# ac_monitor.net
KiCad netlist of a schematic drawn in EAGLE
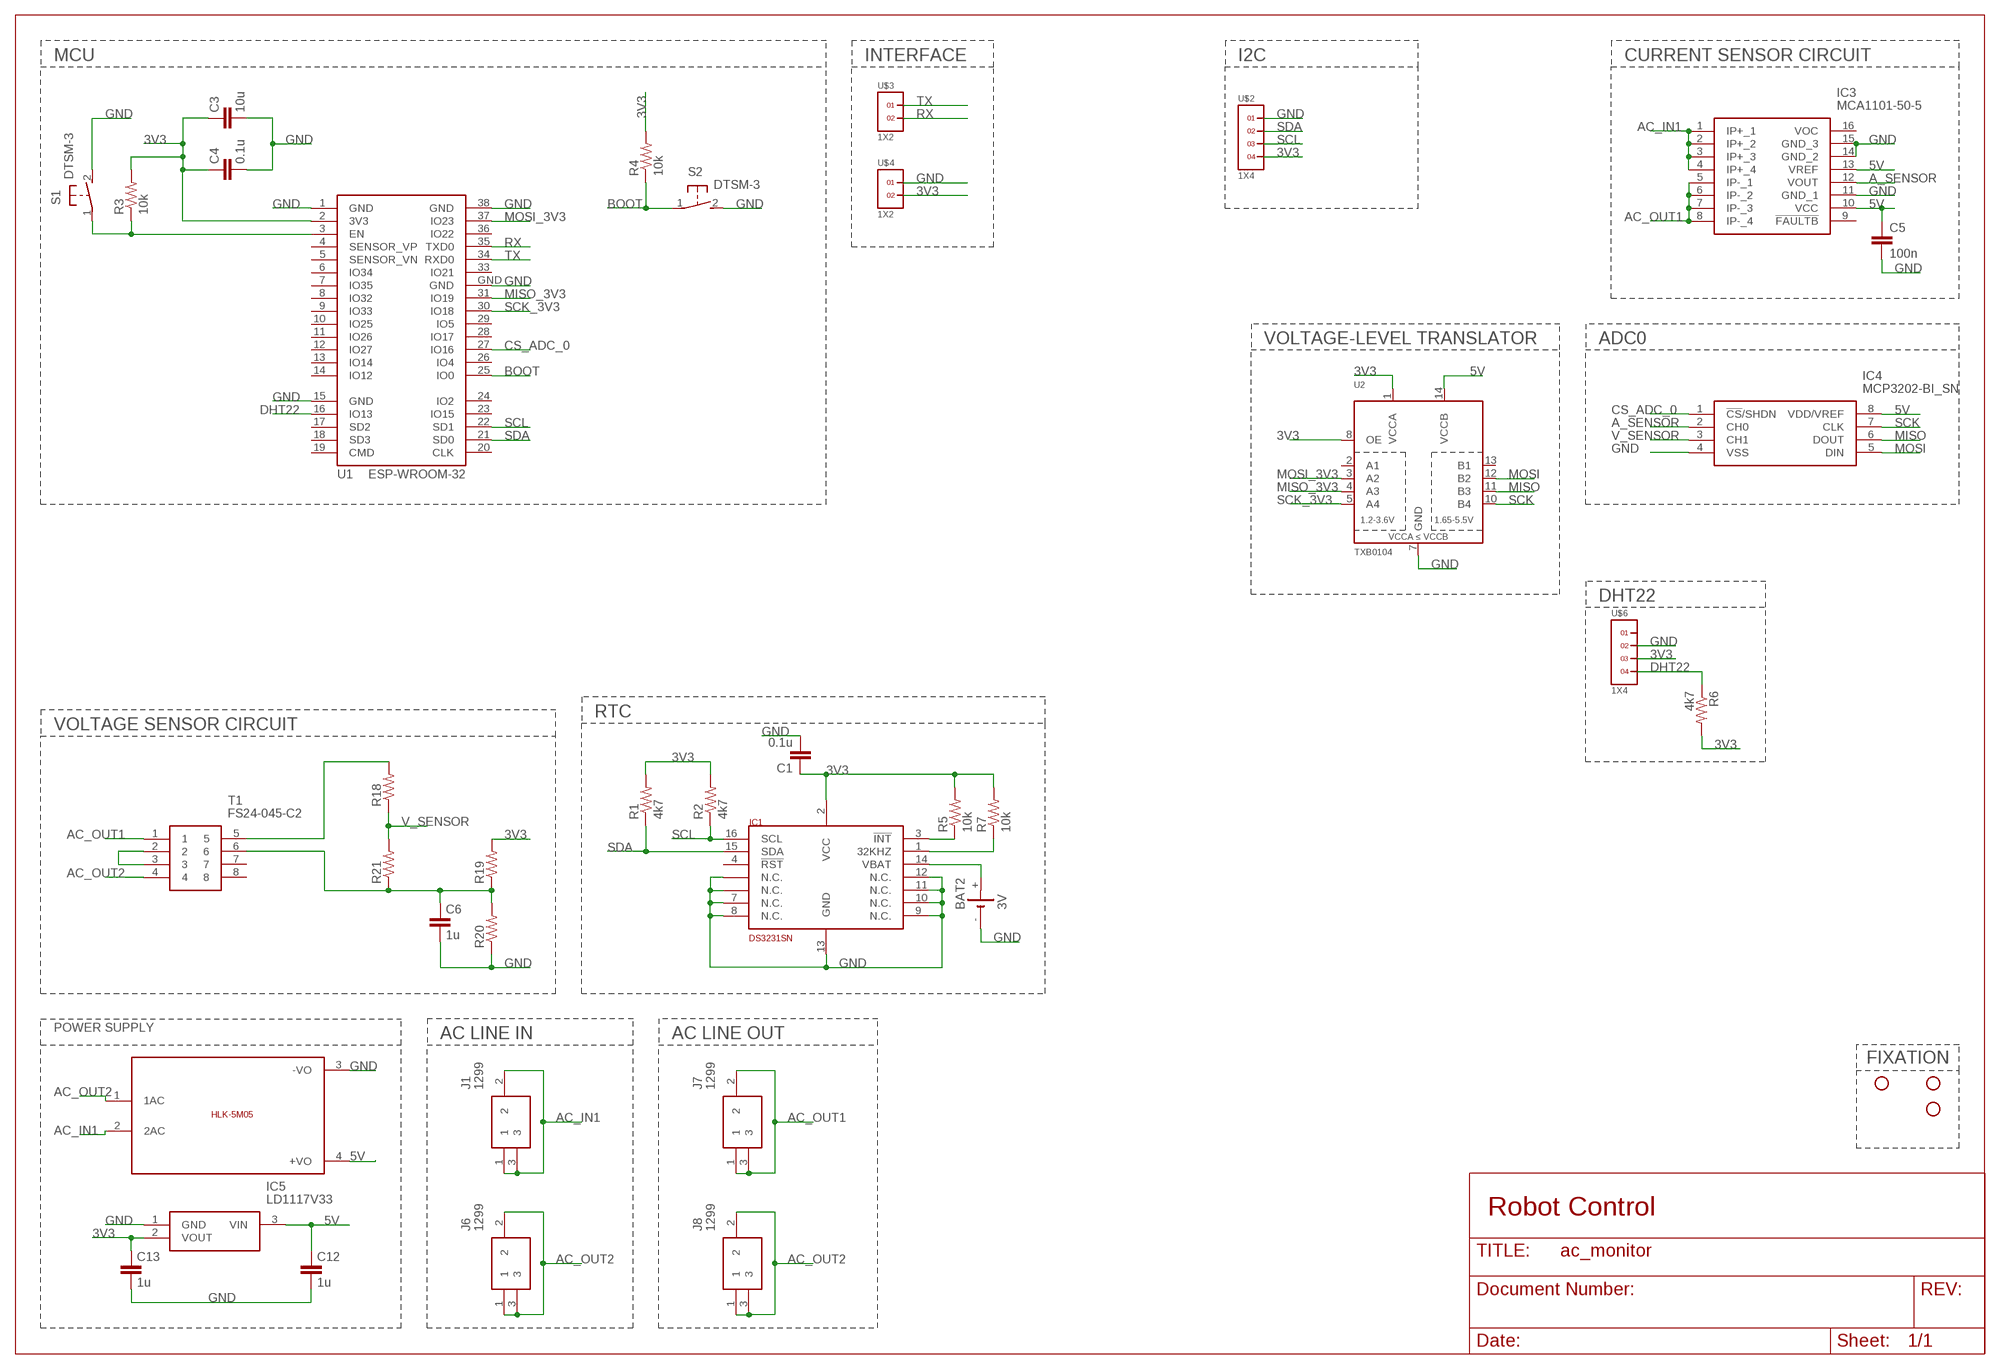
[diagram p0: schematic, sheet 1]

(export (version "E")
  (design (tool "Eeschema 10.0.6"))
  (components
    (comp (ref "BAT2")
      (value "3V")
      (footprint "eagle-import:CH291-1220LF")
      (libsource (lib "eagle-import") (part "CH291-1220LF"))
    )
    (comp (ref "C1")
      (value "0.1u")
      (footprint "eagle-import:C0805K")
      (libsource (lib "eagle-import") (part "C-EUC0805K"))
    )
    (comp (ref "C3")
      (value "10u")
      (footprint "eagle-import:C0805")
      (libsource (lib "eagle-import") (part "C-EUC0805"))
    )
    (comp (ref "C4")
      (value "0.1u")
      (footprint "eagle-import:C0805")
      (libsource (lib "eagle-import") (part "C-EUC0805"))
    )
    (comp (ref "C5")
      (value "100n")
      (footprint "eagle-import:C0805K")
      (libsource (lib "eagle-import") (part "C-EUC0805K"))
    )
    (comp (ref "C6")
      (value "1u")
      (footprint "eagle-import:C0805")
      (libsource (lib "eagle-import") (part "C-EUC0805"))
    )
    (comp (ref "C12")
      (value "1u")
      (footprint "eagle-import:C025-025X050")
      (libsource (lib "eagle-import") (part "C-EU025-025X050"))
    )
    (comp (ref "C13")
      (value "1u")
      (footprint "eagle-import:C025-025X050")
      (libsource (lib "eagle-import") (part "C-EU025-025X050"))
    )
    (comp (ref "IC1")
      (value "DS3231SN")
      (footprint "eagle-import:SO16W")
      (libsource (lib "eagle-import") (part "DS3231SN"))
    )
    (comp (ref "IC3")
      (value "MCA1101-50-5")
      (footprint "eagle-import:SOIC127P1031X264-16N")
      (fields (field (name "MOUSER_PART_NUMBER") "438-MCA1101-50-5"))
      (libsource (lib "eagle-import") (part "MCA1101-50-5"))
    )
    (comp (ref "IC4")
      (value "MCP3202-BI_SN")
      (footprint "eagle-import:SOIC127P600X175-8N")
      (fields
        (field (name "MANUFACTURER_PART_NUMBER") "MCP3202-BI/SN")
        (field (name "MOUSER_PART_NUMBER") "579-MCP3202BISN")
      )
      (libsource (lib "eagle-import") (part "MCP3202-BI_SN"))
    )
    (comp (ref "IC5")
      (value "LD1117V33")
      (footprint "eagle-import:TO270P460X1020X2008-3P")
      (fields (field (name "MOUSER_PART_NUMBER") "511-LD1117V33"))
      (libsource (lib "eagle-import") (part "LD1117V33"))
    )
    (comp (ref "J1")
      (value "1299")
      (footprint "eagle-import:1299")
      (fields (field (name "MOUSER_PART_NUMBER") "534-1299"))
      (libsource (lib "eagle-import") (part "1299"))
    )
    (comp (ref "J6")
      (value "1299")
      (footprint "eagle-import:1299")
      (fields (field (name "MOUSER_PART_NUMBER") "534-1299"))
      (libsource (lib "eagle-import") (part "1299"))
    )
    (comp (ref "J7")
      (value "1299")
      (footprint "eagle-import:1299")
      (fields (field (name "MOUSER_PART_NUMBER") "534-1299"))
      (libsource (lib "eagle-import") (part "1299"))
    )
    (comp (ref "J8")
      (value "1299")
      (footprint "eagle-import:1299")
      (fields (field (name "MOUSER_PART_NUMBER") "534-1299"))
      (libsource (lib "eagle-import") (part "1299"))
    )
    (comp (ref "R1")
      (value "4k7")
      (footprint "eagle-import:R0805")
      (libsource (lib "eagle-import") (part "R-US_R0805"))
    )
    (comp (ref "R2")
      (value "4k7")
      (footprint "eagle-import:R0805")
      (libsource (lib "eagle-import") (part "R-US_R0805"))
    )
    (comp (ref "R3")
      (value "10k")
      (footprint "eagle-import:R0805")
      (libsource (lib "eagle-import") (part "R-US_R0805"))
    )
    (comp (ref "R4")
      (value "10k")
      (footprint "eagle-import:R0805")
      (libsource (lib "eagle-import") (part "R-US_R0805"))
    )
    (comp (ref "R5")
      (value "10k")
      (footprint "eagle-import:R0805")
      (libsource (lib "eagle-import") (part "R-US_R0805"))
    )
    (comp (ref "R6")
      (value "4k7")
      (footprint "eagle-import:R0805")
      (libsource (lib "eagle-import") (part "R-US_R0805"))
    )
    (comp (ref "R7")
      (value "10k")
      (footprint "eagle-import:R0805")
      (libsource (lib "eagle-import") (part "R-US_R0805"))
    )
    (comp (ref "R18")
      (value "270k")
      (footprint "eagle-import:R0805")
      (libsource (lib "eagle-import") (part "R-US_R0805"))
    )
    (comp (ref "R19")
      (value "120k")
      (footprint "eagle-import:R0805")
      (libsource (lib "eagle-import") (part "R-US_R0805"))
    )
    (comp (ref "R20")
      (value "470k")
      (footprint "eagle-import:R0805")
      (libsource (lib "eagle-import") (part "R-US_R0805"))
    )
    (comp (ref "R21")
      (value "33k")
      (footprint "eagle-import:R0805")
      (libsource (lib "eagle-import") (part "R-US_R0805"))
    )
    (comp (ref "S1")
      (value "DTSM-3")
      (footprint "eagle-import:DTSM-3")
      (libsource (lib "eagle-import") (part "DTSM-3"))
    )
    (comp (ref "S2")
      (value "DTSM-3")
      (footprint "eagle-import:DTSM-3")
      (libsource (lib "eagle-import") (part "DTSM-3"))
    )
    (comp (ref "STANDOFF2")
      (value "STAND-OFF")
      (footprint "eagle-import:STAND-OFF")
      (libsource (lib "eagle-import") (part "STAND-OFF"))
    )
    (comp (ref "STANDOFF3")
      (value "STAND-OFF")
      (footprint "eagle-import:STAND-OFF")
      (libsource (lib "eagle-import") (part "STAND-OFF"))
    )
    (comp (ref "STANDOFF4")
      (value "STAND-OFF")
      (footprint "eagle-import:STAND-OFF")
      (libsource (lib "eagle-import") (part "STAND-OFF"))
    )
    (comp (ref "T1")
      (value "FS24-045-C2")
      (footprint "eagle-import:FS24045C2")
      (fields (field (name "MOUSER_PART_NUMBER") "553-FS24-045-C2"))
      (libsource (lib "eagle-import") (part "FS24-045-C2"))
    )
    (comp (ref "U$2")
      (value "1X4")
      (footprint "eagle-import:1X4")
      (libsource (lib "eagle-import") (part "1X4"))
    )
    (comp (ref "U$3")
      (value "1X2")
      (footprint "eagle-import:1X2")
      (libsource (lib "eagle-import") (part "1X2"))
    )
    (comp (ref "U$4")
      (value "1X2")
      (footprint "eagle-import:1X2")
      (libsource (lib "eagle-import") (part "1X2"))
    )
    (comp (ref "U$5")
      (value "5VDC/5W")
      (footprint "eagle-import:HLK-5M05")
      (libsource (lib "eagle-import") (part "HLK-5M05"))
    )
    (comp (ref "U$6")
      (value "1X4")
      (footprint "eagle-import:1X4")
      (libsource (lib "eagle-import") (part "1X4"))
    )
    (comp (ref "U1")
      (value "ESP-WROOM-32")
      (footprint "eagle-import:ESP-WROOM-32")
      (libsource (lib "eagle-import") (part "ESP-WROOM-32"))
    )
    (comp (ref "U2")
      (value "TXB0104")
      (footprint "eagle-import:TSSOP14")
      (libsource (lib "eagle-import") (part "TXB0104PWR"))
    )
  )
  (nets
    (net (code "1") (name "/3V3") (class "Default")
      (node (ref "C1") (pin "1") (pinfunction "1_1") (pintype "passive"))
      (node (ref "C13") (pin "1") (pinfunction "1_1") (pintype "passive"))
      (node (ref "C3") (pin "1") (pinfunction "1_1") (pintype "passive"))
      (node (ref "C4") (pin "1") (pinfunction "1_1") (pintype "passive"))
      (node (ref "IC1") (pin "2") (pinfunction "VCC_2") (pintype "bidirectional"))
      (node (ref "IC5") (pin "2") (pinfunction "VOUT_2") (pintype "output"))
      (node (ref "R1") (pin "2") (pinfunction "2_2") (pintype "passive"))
      (node (ref "R19") (pin "2") (pinfunction "2_2") (pintype "passive"))
      (node (ref "R2") (pin "2") (pinfunction "2_2") (pintype "passive"))
      (node (ref "R3") (pin "2") (pinfunction "2_2") (pintype "passive"))
      (node (ref "R4") (pin "2") (pinfunction "2_2") (pintype "passive"))
      (node (ref "R5") (pin "2") (pinfunction "2_2") (pintype "passive"))
      (node (ref "R6") (pin "2") (pinfunction "2_2") (pintype "passive"))
      (node (ref "R7") (pin "2") (pinfunction "2_2") (pintype "passive"))
      (node (ref "U$2") (pin "4") (pinfunction "4_4") (pintype "bidirectional"))
      (node (ref "U$4") (pin "2") (pinfunction "2_2") (pintype "bidirectional"))
      (node (ref "U$6") (pin "3") (pinfunction "3_3") (pintype "bidirectional"))
      (node (ref "U1") (pin "2") (pinfunction "3V3_2") (pintype "power_in"))
      (node (ref "U2") (pin "1") (pinfunction "VCCA_1") (pintype "bidirectional"))
      (node (ref "U2") (pin "8") (pinfunction "OE_8") (pintype "bidirectional"))
    )
    (net (code "2") (name "/5V") (class "Default")
      (node (ref "C12") (pin "1") (pinfunction "1_1") (pintype "passive"))
      (node (ref "C5") (pin "1") (pinfunction "1_1") (pintype "passive"))
      (node (ref "IC3") (pin "10") (pinfunction "VCC_10") (pintype "bidirectional"))
      (node (ref "IC3") (pin "13") (pinfunction "VREF_13") (pintype "bidirectional"))
      (node (ref "IC4") (pin "8") (pinfunction "VDD/VREF_8") (pintype "power_in"))
      (node (ref "IC5") (pin "3") (pinfunction "VIN_3") (pintype "input"))
      (node (ref "U$5") (pin "4") (pinfunction "+VO_4") (pintype "bidirectional"))
      (node (ref "U2") (pin "14") (pinfunction "VCCB_14") (pintype "bidirectional"))
    )
    (net (code "3") (name "/AC_IN1") (class "Default")
      (node (ref "IC3") (pin "1") (pinfunction "IP+_1_1") (pintype "bidirectional"))
      (node (ref "IC3") (pin "2") (pinfunction "IP+_2_2") (pintype "bidirectional"))
      (node (ref "IC3") (pin "3") (pinfunction "IP+_3_3") (pintype "bidirectional"))
      (node (ref "IC3") (pin "4") (pinfunction "IP+_4_4") (pintype "bidirectional"))
      (node (ref "J1") (pin "1") (pinfunction "1_1") (pintype "bidirectional"))
      (node (ref "J1") (pin "2") (pinfunction "2_2") (pintype "bidirectional"))
      (node (ref "J1") (pin "3") (pinfunction "3_3") (pintype "bidirectional"))
      (node (ref "U$5") (pin "2") (pinfunction "2AC_2") (pintype "bidirectional"))
    )
    (net (code "4") (name "/AC_OUT1") (class "Default")
      (node (ref "IC3") (pin "5") (pinfunction "IP-_1_5") (pintype "bidirectional"))
      (node (ref "IC3") (pin "6") (pinfunction "IP-_2_6") (pintype "bidirectional"))
      (node (ref "IC3") (pin "7") (pinfunction "IP-_3_7") (pintype "bidirectional"))
      (node (ref "IC3") (pin "8") (pinfunction "IP-_4_8") (pintype "bidirectional"))
      (node (ref "J7") (pin "1") (pinfunction "1_1") (pintype "bidirectional"))
      (node (ref "J7") (pin "2") (pinfunction "2_2") (pintype "bidirectional"))
      (node (ref "J7") (pin "3") (pinfunction "3_3") (pintype "bidirectional"))
      (node (ref "T1") (pin "1") (pinfunction "1_1") (pintype "bidirectional"))
    )
    (net (code "5") (name "/AC_OUT2") (class "Default")
      (node (ref "J6") (pin "1") (pinfunction "1_1") (pintype "bidirectional"))
      (node (ref "J6") (pin "2") (pinfunction "2_2") (pintype "bidirectional"))
      (node (ref "J6") (pin "3") (pinfunction "3_3") (pintype "bidirectional"))
      (node (ref "J8") (pin "1") (pinfunction "1_1") (pintype "bidirectional"))
      (node (ref "J8") (pin "2") (pinfunction "2_2") (pintype "bidirectional"))
      (node (ref "J8") (pin "3") (pinfunction "3_3") (pintype "bidirectional"))
      (node (ref "T1") (pin "4") (pinfunction "4_4") (pintype "bidirectional"))
      (node (ref "U$5") (pin "1") (pinfunction "1AC_1") (pintype "bidirectional"))
    )
    (net (code "6") (name "/A_SENSOR") (class "Default")
      (node (ref "IC3") (pin "12") (pinfunction "VOUT_12") (pintype "bidirectional"))
      (node (ref "IC4") (pin "2") (pinfunction "CH0_2") (pintype "bidirectional"))
    )
    (net (code "7") (name "/BOOT") (class "Default")
      (node (ref "R4") (pin "1") (pinfunction "1_1") (pintype "passive"))
      (node (ref "S2") (pin "1") (pinfunction "1_1") (pintype "passive"))
      (node (ref "U1") (pin "25") (pinfunction "IO0_25") (pintype "bidirectional"))
    )
    (net (code "8") (name "/CS_ADC_0") (class "Default")
      (node (ref "IC4") (pin "1") (pinfunction "~{CS}/SHDN_1") (pintype "input"))
      (node (ref "U1") (pin "27") (pinfunction "IO16_27") (pintype "bidirectional"))
    )
    (net (code "9") (name "/DHT22") (class "Default")
      (node (ref "R6") (pin "1") (pinfunction "1_1") (pintype "passive"))
      (node (ref "U$6") (pin "4") (pinfunction "4_4") (pintype "bidirectional"))
      (node (ref "U1") (pin "16") (pinfunction "IO13_16") (pintype "bidirectional"))
    )
    (net (code "10") (name "/GND") (class "Default")
      (node (ref "BAT2") (pin "-") (pinfunction "-_-") (pintype "passive"))
      (node (ref "C1") (pin "2") (pinfunction "2_2") (pintype "passive"))
      (node (ref "C12") (pin "2") (pinfunction "2_2") (pintype "passive"))
      (node (ref "C13") (pin "2") (pinfunction "2_2") (pintype "passive"))
      (node (ref "C3") (pin "2") (pinfunction "2_2") (pintype "passive"))
      (node (ref "C4") (pin "2") (pinfunction "2_2") (pintype "passive"))
      (node (ref "C5") (pin "2") (pinfunction "2_2") (pintype "passive"))
      (node (ref "C6") (pin "2") (pinfunction "2_2") (pintype "passive"))
      (node (ref "IC1") (pin "10") (pinfunction "N.C._10") (pintype "bidirectional"))
      (node (ref "IC1") (pin "11") (pinfunction "N.C._11") (pintype "bidirectional"))
      (node (ref "IC1") (pin "12") (pinfunction "N.C._12") (pintype "bidirectional"))
      (node (ref "IC1") (pin "13") (pinfunction "GND_13") (pintype "bidirectional"))
      (node (ref "IC1") (pin "5") (pinfunction "N.C._5") (pintype "bidirectional"))
      (node (ref "IC1") (pin "6") (pinfunction "N.C._6") (pintype "bidirectional"))
      (node (ref "IC1") (pin "7") (pinfunction "N.C._7") (pintype "bidirectional"))
      (node (ref "IC1") (pin "8") (pinfunction "N.C._8") (pintype "bidirectional"))
      (node (ref "IC1") (pin "9") (pinfunction "N.C._9") (pintype "bidirectional"))
      (node (ref "IC3") (pin "11") (pinfunction "GND_1_11") (pintype "bidirectional"))
      (node (ref "IC3") (pin "14") (pinfunction "GND_2_14") (pintype "bidirectional"))
      (node (ref "IC3") (pin "15") (pinfunction "GND_3_15") (pintype "bidirectional"))
      (node (ref "IC4") (pin "4") (pinfunction "VSS_4") (pintype "power_in"))
      (node (ref "IC5") (pin "1") (pinfunction "GND_1") (pintype "power_in"))
      (node (ref "R20") (pin "1") (pinfunction "1_1") (pintype "passive"))
      (node (ref "S1") (pin "2") (pinfunction "2_2") (pintype "passive"))
      (node (ref "S2") (pin "2") (pinfunction "2_2") (pintype "passive"))
      (node (ref "U$2") (pin "1") (pinfunction "1_1") (pintype "bidirectional"))
      (node (ref "U$4") (pin "1") (pinfunction "1_1") (pintype "bidirectional"))
      (node (ref "U$5") (pin "3") (pinfunction "-VO_3") (pintype "bidirectional"))
      (node (ref "U$6") (pin "2") (pinfunction "2_2") (pintype "bidirectional"))
      (node (ref "U1") (pin "1") (pinfunction "GND_1") (pintype "power_in"))
      (node (ref "U1") (pin "15") (pinfunction "GND_15") (pintype "power_in"))
      (node (ref "U1") (pin "38") (pinfunction "GND_38") (pintype "power_in"))
      (node (ref "U1") (pin "GND") (pinfunction "GND_GND") (pintype "power_in"))
      (node (ref "U2") (pin "7") (pinfunction "GND_7") (pintype "bidirectional"))
    )
    (net (code "11") (name "/MISO") (class "Default")
      (node (ref "IC4") (pin "6") (pinfunction "DOUT_6") (pintype "output"))
      (node (ref "U2") (pin "11") (pinfunction "B3_11") (pintype "bidirectional"))
    )
    (net (code "12") (name "/MISO_3V3") (class "Default")
      (node (ref "U1") (pin "31") (pinfunction "IO19_31") (pintype "bidirectional"))
      (node (ref "U2") (pin "4") (pinfunction "A3_4") (pintype "bidirectional"))
    )
    (net (code "13") (name "/MOSI") (class "Default")
      (node (ref "IC4") (pin "5") (pinfunction "DIN_5") (pintype "input"))
      (node (ref "U2") (pin "12") (pinfunction "B2_12") (pintype "bidirectional"))
    )
    (net (code "14") (name "/MOSI_3V3") (class "Default")
      (node (ref "U1") (pin "37") (pinfunction "IO23_37") (pintype "bidirectional"))
      (node (ref "U2") (pin "3") (pinfunction "A2_3") (pintype "bidirectional"))
    )
    (net (code "15") (name "/RX") (class "Default")
      (node (ref "U$3") (pin "2") (pinfunction "2_2") (pintype "bidirectional"))
      (node (ref "U1") (pin "35") (pinfunction "TXD0_35") (pintype "bidirectional"))
    )
    (net (code "16") (name "/SCK") (class "Default")
      (node (ref "IC4") (pin "7") (pinfunction "CLK_7") (pintype "input"))
      (node (ref "U2") (pin "10") (pinfunction "B4_10") (pintype "bidirectional"))
    )
    (net (code "17") (name "/SCK_3V3") (class "Default")
      (node (ref "U1") (pin "30") (pinfunction "IO18_30") (pintype "bidirectional"))
      (node (ref "U2") (pin "5") (pinfunction "A4_5") (pintype "bidirectional"))
    )
    (net (code "18") (name "/SCL") (class "Default")
      (node (ref "IC1") (pin "16") (pinfunction "SCL_16") (pintype "bidirectional"))
      (node (ref "R2") (pin "1") (pinfunction "1_1") (pintype "passive"))
      (node (ref "U$2") (pin "3") (pinfunction "3_3") (pintype "bidirectional"))
      (node (ref "U1") (pin "22") (pinfunction "SD1_22") (pintype "bidirectional"))
    )
    (net (code "19") (name "/SDA") (class "Default")
      (node (ref "IC1") (pin "15") (pinfunction "SDA_15") (pintype "bidirectional"))
      (node (ref "R1") (pin "1") (pinfunction "1_1") (pintype "passive"))
      (node (ref "U$2") (pin "2") (pinfunction "2_2") (pintype "bidirectional"))
      (node (ref "U1") (pin "21") (pinfunction "SD0_21") (pintype "bidirectional"))
    )
    (net (code "20") (name "/TX") (class "Default")
      (node (ref "U$3") (pin "1") (pinfunction "1_1") (pintype "bidirectional"))
      (node (ref "U1") (pin "34") (pinfunction "RXD0_34") (pintype "bidirectional"))
    )
    (net (code "21") (name "/V_SENSOR") (class "Default")
      (node (ref "IC4") (pin "3") (pinfunction "CH1_3") (pintype "bidirectional"))
      (node (ref "R18") (pin "1") (pinfunction "1_1") (pintype "passive"))
      (node (ref "R21") (pin "2") (pinfunction "2_2") (pintype "passive"))
    )
    (net (code "22") (name "Net-(C6-Pad1)") (class "Default")
      (node (ref "C6") (pin "1") (pinfunction "1_1") (pintype "passive"))
      (node (ref "R19") (pin "1") (pinfunction "1_1") (pintype "passive"))
      (node (ref "R20") (pin "2") (pinfunction "2_2") (pintype "passive"))
      (node (ref "R21") (pin "1") (pinfunction "1_1") (pintype "passive"))
      (node (ref "T1") (pin "6") (pinfunction "6_6") (pintype "bidirectional"))
    )
    (net (code "23") (name "Net-(IC1-32KHZ)") (class "Default")
      (node (ref "IC1") (pin "1") (pinfunction "32KHZ_1") (pintype "bidirectional"))
      (node (ref "R7") (pin "1") (pinfunction "1_1") (pintype "passive"))
    )
    (net (code "24") (name "Net-(IC1-VBAT)") (class "Default")
      (node (ref "BAT2") (pin "+") (pinfunction "+_+") (pintype "passive"))
      (node (ref "IC1") (pin "14") (pinfunction "VBAT_14") (pintype "bidirectional"))
    )
    (net (code "25") (name "Net-(IC1-~{INT})") (class "Default")
      (node (ref "IC1") (pin "3") (pinfunction "~{INT}_3") (pintype "bidirectional"))
      (node (ref "R5") (pin "1") (pinfunction "1_1") (pintype "passive"))
    )
    (net (code "26") (name "Net-(R18-Pad2)") (class "Default")
      (node (ref "R18") (pin "2") (pinfunction "2_2") (pintype "passive"))
      (node (ref "T1") (pin "5") (pinfunction "5_5") (pintype "bidirectional"))
    )
    (net (code "27") (name "Net-(T1-Pad2)") (class "Default")
      (node (ref "T1") (pin "2") (pinfunction "2_2") (pintype "bidirectional"))
      (node (ref "T1") (pin "3") (pinfunction "3_3") (pintype "bidirectional"))
    )
    (net (code "28") (name "Net-(U1-EN)") (class "Default")
      (node (ref "R3") (pin "1") (pinfunction "1_1") (pintype "passive"))
      (node (ref "S1") (pin "1") (pinfunction "1_1") (pintype "passive"))
      (node (ref "U1") (pin "3") (pinfunction "EN_3") (pintype "input"))
    )
    (net (code "29") (name "unconnected-(IC1-~{RST}-Pad4)") (class "Default")
      (node (ref "IC1") (pin "4") (pinfunction "~{RST}_4") (pintype "bidirectional"))
    )
    (net (code "30") (name "unconnected-(IC3-VOC-Pad16)") (class "Default")
      (node (ref "IC3") (pin "16") (pinfunction "VOC_16") (pintype "bidirectional"))
    )
    (net (code "31") (name "unconnected-(IC3-~{FAULTB}-Pad9)") (class "Default")
      (node (ref "IC3") (pin "9") (pinfunction "~{FAULTB}_9") (pintype "bidirectional"))
    )
    (net (code "32") (name "unconnected-(T1-Pad7)") (class "Default")
      (node (ref "T1") (pin "7") (pinfunction "7_7") (pintype "bidirectional"))
    )
    (net (code "33") (name "unconnected-(T1-Pad8)") (class "Default")
      (node (ref "T1") (pin "8") (pinfunction "8_8") (pintype "bidirectional"))
    )
    (net (code "34") (name "unconnected-(U$6-Pad1)") (class "Default")
      (node (ref "U$6") (pin "1") (pinfunction "1_1") (pintype "bidirectional"))
    )
    (net (code "35") (name "unconnected-(U1-CLK-Pad20)") (class "Default")
      (node (ref "U1") (pin "20") (pinfunction "CLK_20") (pintype "bidirectional"))
    )
    (net (code "36") (name "unconnected-(U1-CMD-Pad19)") (class "Default")
      (node (ref "U1") (pin "19") (pinfunction "CMD_19") (pintype "bidirectional"))
    )
    (net (code "37") (name "unconnected-(U1-IO2-Pad24)") (class "Default")
      (node (ref "U1") (pin "24") (pinfunction "IO2_24") (pintype "bidirectional"))
    )
    (net (code "38") (name "unconnected-(U1-IO4-Pad26)") (class "Default")
      (node (ref "U1") (pin "26") (pinfunction "IO4_26") (pintype "bidirectional"))
    )
    (net (code "39") (name "unconnected-(U1-IO5-Pad29)") (class "Default")
      (node (ref "U1") (pin "29") (pinfunction "IO5_29") (pintype "bidirectional"))
    )
    (net (code "40") (name "unconnected-(U1-IO12-Pad14)") (class "Default")
      (node (ref "U1") (pin "14") (pinfunction "IO12_14") (pintype "bidirectional"))
    )
    (net (code "41") (name "unconnected-(U1-IO14-Pad13)") (class "Default")
      (node (ref "U1") (pin "13") (pinfunction "IO14_13") (pintype "bidirectional"))
    )
    (net (code "42") (name "unconnected-(U1-IO15-Pad23)") (class "Default")
      (node (ref "U1") (pin "23") (pinfunction "IO15_23") (pintype "bidirectional"))
    )
    (net (code "43") (name "unconnected-(U1-IO17-Pad28)") (class "Default")
      (node (ref "U1") (pin "28") (pinfunction "IO17_28") (pintype "bidirectional"))
    )
    (net (code "44") (name "unconnected-(U1-IO21-Pad33)") (class "Default")
      (node (ref "U1") (pin "33") (pinfunction "IO21_33") (pintype "bidirectional"))
    )
    (net (code "45") (name "unconnected-(U1-IO22-Pad36)") (class "Default")
      (node (ref "U1") (pin "36") (pinfunction "IO22_36") (pintype "bidirectional"))
    )
    (net (code "46") (name "unconnected-(U1-IO25-Pad10)") (class "Default")
      (node (ref "U1") (pin "10") (pinfunction "IO25_10") (pintype "bidirectional"))
    )
    (net (code "47") (name "unconnected-(U1-IO26-Pad11)") (class "Default")
      (node (ref "U1") (pin "11") (pinfunction "IO26_11") (pintype "bidirectional"))
    )
    (net (code "48") (name "unconnected-(U1-IO27-Pad12)") (class "Default")
      (node (ref "U1") (pin "12") (pinfunction "IO27_12") (pintype "bidirectional"))
    )
    (net (code "49") (name "unconnected-(U1-IO32-Pad8)") (class "Default")
      (node (ref "U1") (pin "8") (pinfunction "IO32_8") (pintype "bidirectional"))
    )
    (net (code "50") (name "unconnected-(U1-IO33-Pad9)") (class "Default")
      (node (ref "U1") (pin "9") (pinfunction "IO33_9") (pintype "bidirectional"))
    )
    (net (code "51") (name "unconnected-(U1-IO34-Pad6)") (class "Default")
      (node (ref "U1") (pin "6") (pinfunction "IO34_6") (pintype "bidirectional"))
    )
    (net (code "52") (name "unconnected-(U1-IO35-Pad7)") (class "Default")
      (node (ref "U1") (pin "7") (pinfunction "IO35_7") (pintype "bidirectional"))
    )
    (net (code "53") (name "unconnected-(U1-SD2-Pad17)") (class "Default")
      (node (ref "U1") (pin "17") (pinfunction "SD2_17") (pintype "bidirectional"))
    )
    (net (code "54") (name "unconnected-(U1-SD3-Pad18)") (class "Default")
      (node (ref "U1") (pin "18") (pinfunction "SD3_18") (pintype "bidirectional"))
    )
    (net (code "55") (name "unconnected-(U1-SENSOR_VN-Pad5)") (class "Default")
      (node (ref "U1") (pin "5") (pinfunction "SENSOR_VN_5") (pintype "bidirectional"))
    )
    (net (code "56") (name "unconnected-(U1-SENSOR_VP-Pad4)") (class "Default")
      (node (ref "U1") (pin "4") (pinfunction "SENSOR_VP_4") (pintype "bidirectional"))
    )
    (net (code "57") (name "unconnected-(U2-A1-Pad2)") (class "Default")
      (node (ref "U2") (pin "2") (pinfunction "A1_2") (pintype "bidirectional"))
    )
    (net (code "58") (name "unconnected-(U2-B1-Pad13)") (class "Default")
      (node (ref "U2") (pin "13") (pinfunction "B1_13") (pintype "bidirectional"))
    )
  )
)
